# Voltage_Meter.net
KiCad netlist of a schematic drawn in Altium Designer
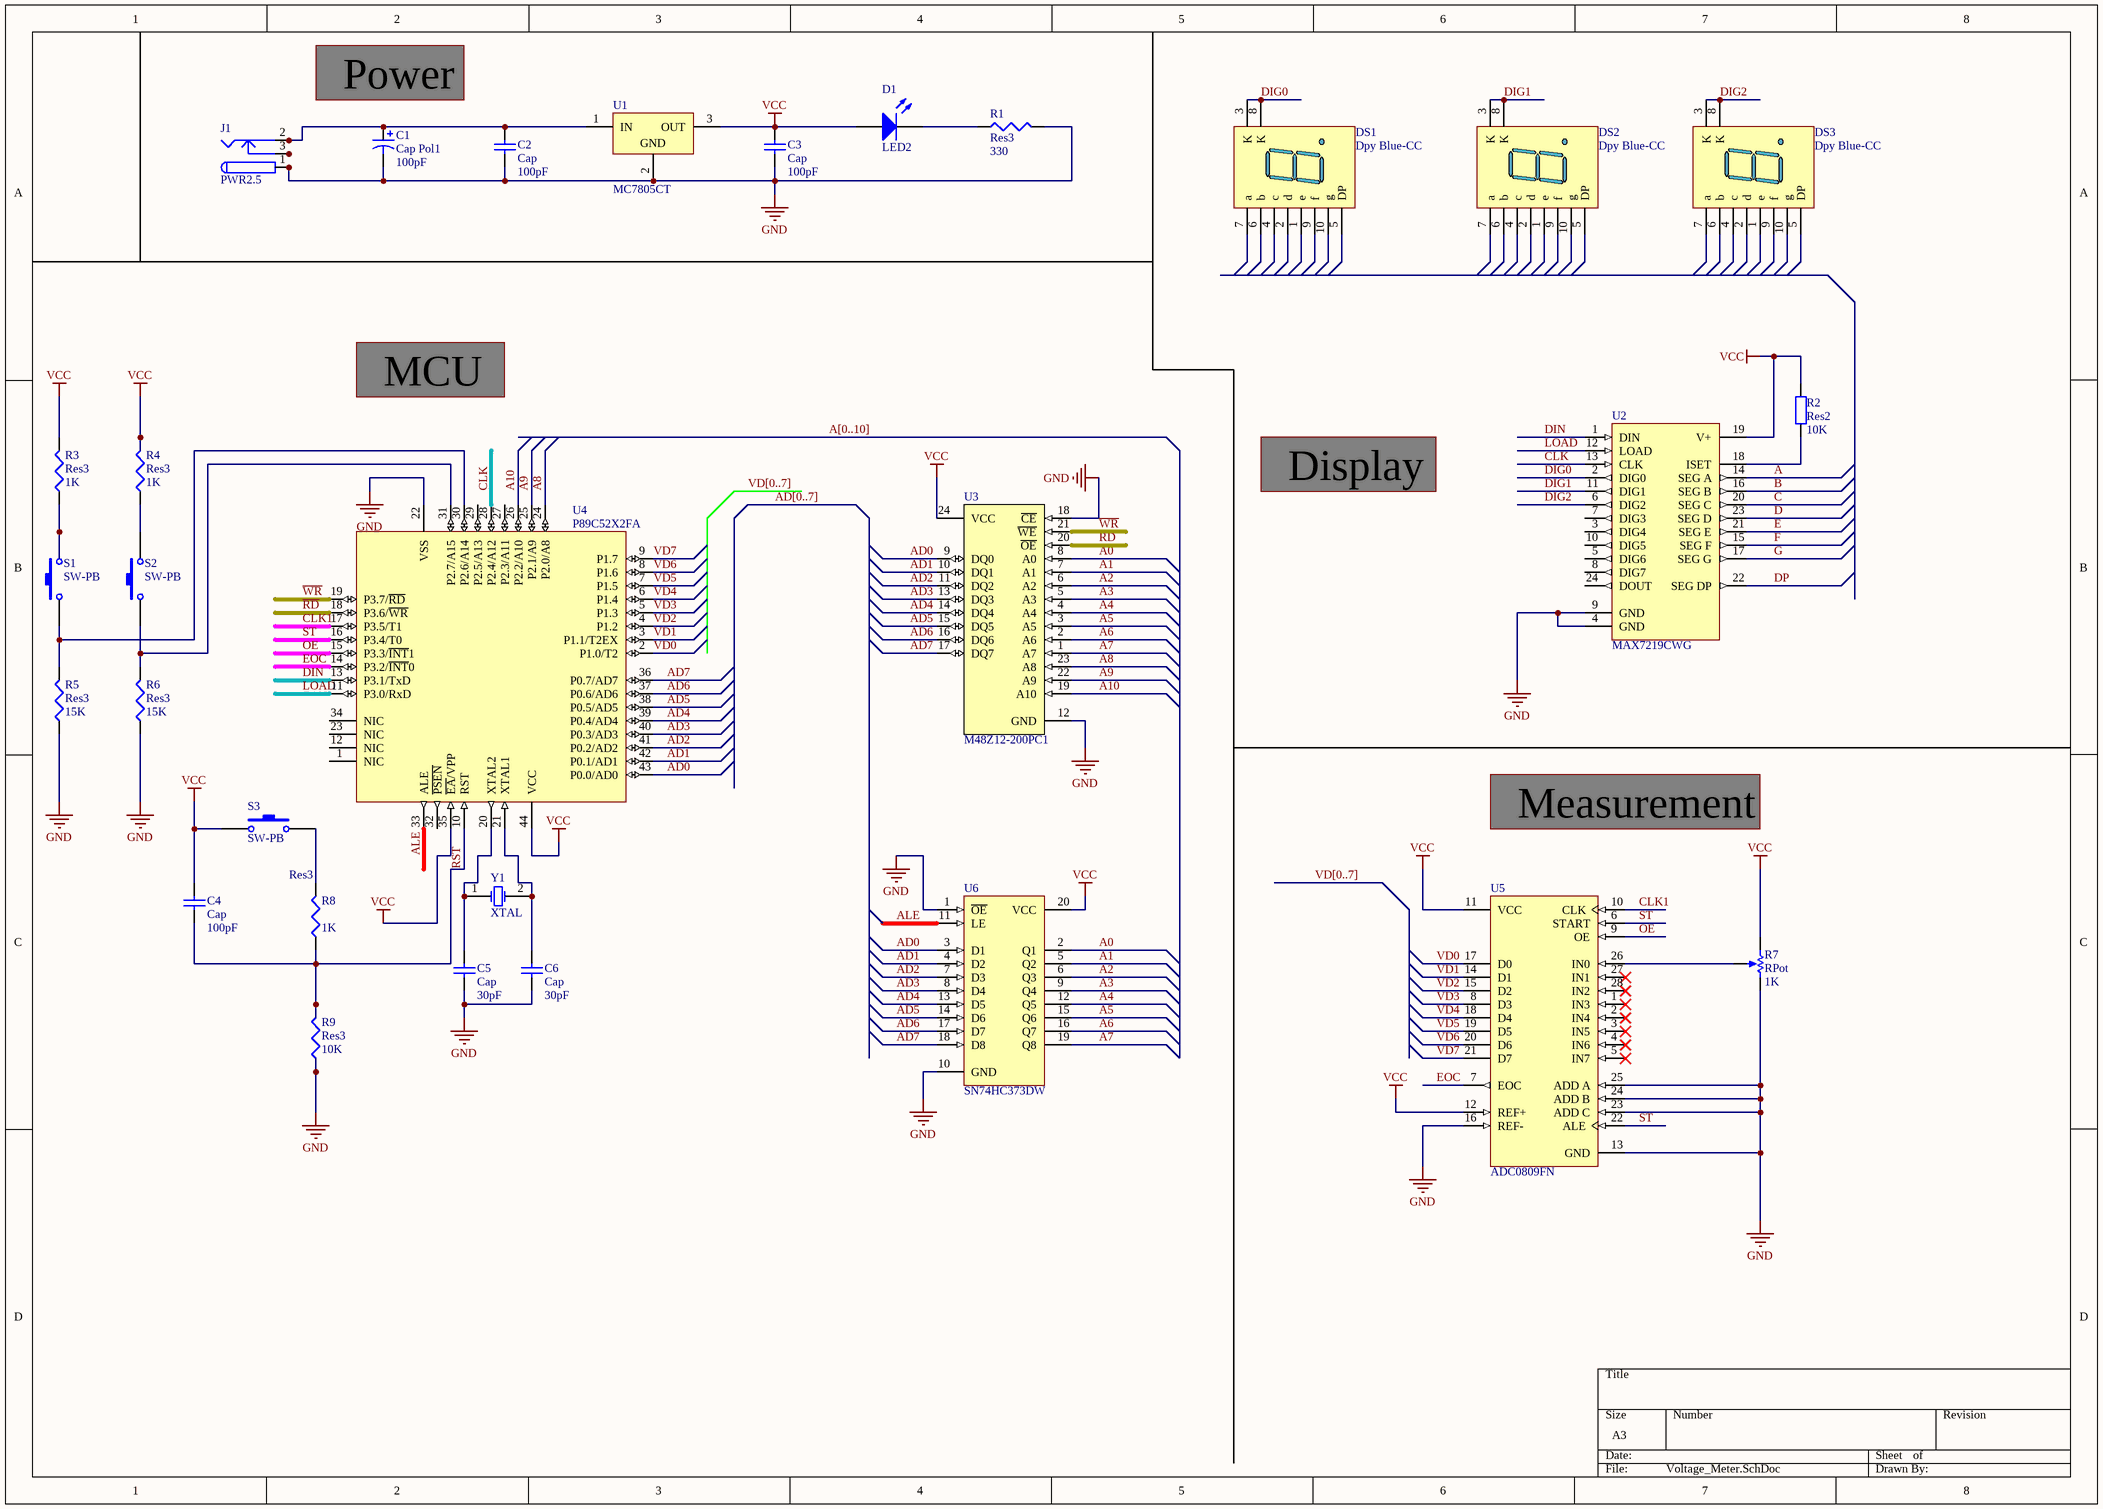
[diagram p0: Voltage_Meter.SchDoc]

(export (version "E")
  (design (tool "Eeschema 10.0.6"))
  (components
    (comp (ref "C1")
      (value "Cap Pol1")
      (footprint "RB7.6-15")
      (description "Polarized Capacitor (Radial)")
      (fields (field (name "ALTIUM_VALUE") "100pF") (field (name "PUBLISHER") "Altium Limited"))
      (libsource (lib "Miscellaneous Devices") (part "Cap Pol1"))
    )
    (comp (ref "C2")
      (value "Cap")
      (footprint "RAD-0.3")
      (description "Capacitor")
      (fields (field (name "ALTIUM_VALUE") "100pF") (field (name "PUBLISHER") "Altium Limited"))
      (libsource (lib "Miscellaneous Devices") (part "Cap"))
    )
    (comp (ref "C3")
      (value "Cap")
      (footprint "RAD-0.3")
      (description "Capacitor")
      (fields (field (name "ALTIUM_VALUE") "100pF") (field (name "PUBLISHER") "Altium Limited"))
      (libsource (lib "Miscellaneous Devices") (part "Cap"))
    )
    (comp (ref "C4")
      (value "Cap")
      (footprint "RAD-0.3")
      (description "Capacitor")
      (fields (field (name "ALTIUM_VALUE") "100pF") (field (name "PUBLISHER") "Altium Limited"))
      (libsource (lib "Miscellaneous Devices") (part "Cap"))
    )
    (comp (ref "C5")
      (value "Cap")
      (footprint "RAD-0.3")
      (description "Capacitor")
      (fields (field (name "ALTIUM_VALUE") "30pF") (field (name "PUBLISHER") "Altium Limited"))
      (libsource (lib "Miscellaneous Devices") (part "Cap"))
    )
    (comp (ref "C6")
      (value "Cap")
      (footprint "RAD-0.3")
      (description "Capacitor")
      (fields (field (name "ALTIUM_VALUE") "30pF") (field (name "PUBLISHER") "Altium Limited"))
      (libsource (lib "Miscellaneous Devices") (part "Cap"))
    )
    (comp (ref "D1")
      (value "LED2")
      (footprint "3.2X1.6X1.1")
      (description "Typical RED, GREEN, YELLOW, AMBER GaAs LED")
      (fields (field (name "PUBLISHER") "Altium Limited"))
      (libsource (lib "Miscellaneous Devices") (part "LED2"))
    )
    (comp (ref "DS1")
      (value "Dpy Blue-CC")
      (footprint "H")
      (description "14.2 mm General Purpose Blue 7-Segment Display: CC, RH DP, Gray Surface")
      (fields (field (name "PUBLISHER") "Altium Limited"))
      (libsource (lib "Miscellaneous Devices") (part "Dpy Blue-CC"))
    )
    (comp (ref "DS2")
      (value "Dpy Blue-CC")
      (footprint "H")
      (description "14.2 mm General Purpose Blue 7-Segment Display: CC, RH DP, Gray Surface")
      (fields (field (name "PUBLISHER") "Altium Limited"))
      (libsource (lib "Miscellaneous Devices") (part "Dpy Blue-CC"))
    )
    (comp (ref "DS3")
      (value "Dpy Blue-CC")
      (footprint "H")
      (description "14.2 mm General Purpose Blue 7-Segment Display: CC, RH DP, Gray Surface")
      (fields (field (name "PUBLISHER") "Altium Limited"))
      (libsource (lib "Miscellaneous Devices") (part "Dpy Blue-CC"))
    )
    (comp (ref "J1")
      (value "PWR2.5")
      (footprint "KLD-0202")
      (description "Low Voltage Power Supply Connector")
      (fields (field (name "PUBLISHER") "Altium Limited"))
      (libsource (lib "Miscellaneous Connectors") (part "PWR2.5"))
    )
    (comp (ref "R1")
      (value "Res3")
      (footprint "J1-0603")
      (description "Resistor")
      (fields (field (name "ALTIUM_VALUE") "330") (field (name "PUBLISHER") "Altium Limited"))
      (libsource (lib "Miscellaneous Devices") (part "Res3"))
    )
    (comp (ref "R2")
      (value "Res2")
      (footprint "AXIAL-0.4")
      (description "Resistor")
      (fields (field (name "ALTIUM_VALUE") "10K") (field (name "PUBLISHER") "Altium Limited"))
      (libsource (lib "Miscellaneous Devices") (part "Res2"))
    )
    (comp (ref "R3")
      (value "Res3")
      (footprint "J1-0603")
      (description "Resistor")
      (fields (field (name "ALTIUM_VALUE") "1K") (field (name "PUBLISHER") "Altium Limited"))
      (libsource (lib "Miscellaneous Devices") (part "Res3"))
    )
    (comp (ref "R4")
      (value "Res3")
      (footprint "J1-0603")
      (description "Resistor")
      (fields (field (name "ALTIUM_VALUE") "1K") (field (name "PUBLISHER") "Altium Limited"))
      (libsource (lib "Miscellaneous Devices") (part "Res3"))
    )
    (comp (ref "R5")
      (value "Res3")
      (footprint "J1-0603")
      (description "Resistor")
      (fields (field (name "ALTIUM_VALUE") "15K") (field (name "PUBLISHER") "Altium Limited"))
      (libsource (lib "Miscellaneous Devices") (part "Res3"))
    )
    (comp (ref "R6")
      (value "Res3")
      (footprint "J1-0603")
      (description "Resistor")
      (fields (field (name "ALTIUM_VALUE") "15K") (field (name "PUBLISHER") "Altium Limited"))
      (libsource (lib "Miscellaneous Devices") (part "Res3"))
    )
    (comp (ref "R7")
      (value "RPot")
      (footprint "VR5")
      (description "Potentiometer")
      (fields (field (name "ALTIUM_VALUE") "1K") (field (name "PUBLISHER") "Altium Limited"))
      (libsource (lib "Miscellaneous Devices") (part "RPot"))
    )
    (comp (ref "R8")
      (value "Res3")
      (footprint "J1-0603")
      (description "Resistor")
      (fields (field (name "ALTIUM_VALUE") "1K") (field (name "PUBLISHER") "Altium Limited"))
      (libsource (lib "Miscellaneous Devices") (part "Res3"))
    )
    (comp (ref "R9")
      (value "Res3")
      (footprint "J1-0603")
      (description "Resistor")
      (fields (field (name "ALTIUM_VALUE") "10K") (field (name "PUBLISHER") "Altium Limited"))
      (libsource (lib "Miscellaneous Devices") (part "Res3"))
    )
    (comp (ref "S1")
      (value "SW-PB")
      (footprint "SPST-2")
      (description "Switch")
      (fields (field (name "PUBLISHER") "Altium Limited"))
      (libsource (lib "Miscellaneous Devices") (part "SW-PB"))
    )
    (comp (ref "S2")
      (value "SW-PB")
      (footprint "SPST-2")
      (description "Switch")
      (fields (field (name "PUBLISHER") "Altium Limited"))
      (libsource (lib "Miscellaneous Devices") (part "SW-PB"))
    )
    (comp (ref "S3")
      (value "SW-PB")
      (footprint "SPST-2")
      (description "Switch")
      (fields (field (name "PUBLISHER") "Altium Limited"))
      (libsource (lib "Miscellaneous Devices") (part "SW-PB"))
    )
    (comp (ref "U1")
      (value "MC7805CT")
      (footprint "221A-04")
      (description "3-Terminal Positive Fixed Voltage Regulator")
      (fields (field (name "PUBLISHER") "Altium Limited"))
      (libsource (lib "Motorola Power Mgt Voltage Regulator") (part "MC7805CT"))
    )
    (comp (ref "U2")
      (value "MAX7219CWG")
      (footprint "WSO24_N")
      (description "Serially Interfaced, 8-Digit LED Display Driver")
      (fields (field (name "PUBLISHER") "Altium Limited"))
      (libsource (lib "Maxim Interface Display Driver") (part "MAX7219CWG"))
    )
    (comp (ref "U3")
      (value "M48Z12-200PC1")
      (footprint "PCDIP24")
      (description "16 Kbit (2Kb x 8) Zeropower SRAM")
      (fields (field (name "PUBLISHER") "Altium Limited"))
      (libsource (lib "ST Memory Non-Volatile RAM") (part "M48Z12-200PC1"))
    )
    (comp (ref "U4")
      (value "P89C52X2FA")
      (footprint "SOT187-2_N")
      (description "80C51 8-Bit Flash Microcontroller Family, 8 kB Flash")
      (fields (field (name "PUBLISHER") "Altium Limited"))
      (libsource (lib "Philips Microcontroller 8-Bit") (part "P89C52X2FA"))
    )
    (comp (ref "U5")
      (value "ADC0809FN")
      (footprint "FN028_N")
      (description "CMOS Analog-to-Digital Converter with 8-Channel Multiplexer")
      (fields (field (name "PUBLISHER") "Altium Limited"))
      (libsource (lib "TI Converter Analog to Digital") (part "ADC0809FN"))
    )
    (comp (ref "U6")
      (value "SN74HC373DW")
      (footprint "DW020_N")
      (description "Octal Transparent D-Type Latches with 3-State Outputs")
      (fields (field (name "PUBLISHER") "Altium Limited"))
      (libsource (lib "TI Logic Latch") (part "SN74HC373DW"))
    )
    (comp (ref "Y1")
      (value "XTAL")
      (footprint "R38")
      (description "Crystal Oscillator")
      (fields (field (name "PUBLISHER") "Altium Limited"))
      (libsource (lib "Miscellaneous Devices") (part "XTAL"))
    )
  )
  (nets
    (net (code "1") (name "/A") (class "Default")
      (node (ref "U2") (pin "14") (pinfunction "SEG_A_14") (pintype "output"))
    )
    (net (code "2") (name "/A0") (class "Default")
      (node (ref "U3") (pin "8") (pinfunction "A0_8") (pintype "input"))
      (node (ref "U6") (pin "2") (pinfunction "Q1_2") (pintype "tri_state"))
    )
    (net (code "3") (name "/A1") (class "Default")
      (node (ref "U3") (pin "7") (pinfunction "A1_7") (pintype "input"))
      (node (ref "U6") (pin "5") (pinfunction "Q2_5") (pintype "tri_state"))
    )
    (net (code "4") (name "/A2") (class "Default")
      (node (ref "U3") (pin "6") (pinfunction "A2_6") (pintype "input"))
      (node (ref "U6") (pin "6") (pinfunction "Q3_6") (pintype "tri_state"))
    )
    (net (code "5") (name "/A3") (class "Default")
      (node (ref "U3") (pin "5") (pinfunction "A3_5") (pintype "input"))
      (node (ref "U6") (pin "9") (pinfunction "Q4_9") (pintype "tri_state"))
    )
    (net (code "6") (name "/A4") (class "Default")
      (node (ref "U3") (pin "4") (pinfunction "A4_4") (pintype "input"))
      (node (ref "U6") (pin "12") (pinfunction "Q5_12") (pintype "tri_state"))
    )
    (net (code "7") (name "/A5") (class "Default")
      (node (ref "U3") (pin "3") (pinfunction "A5_3") (pintype "input"))
      (node (ref "U6") (pin "15") (pinfunction "Q6_15") (pintype "tri_state"))
    )
    (net (code "8") (name "/A6") (class "Default")
      (node (ref "U3") (pin "2") (pinfunction "A6_2") (pintype "input"))
      (node (ref "U6") (pin "16") (pinfunction "Q7_16") (pintype "tri_state"))
    )
    (net (code "9") (name "/A7") (class "Default")
      (node (ref "U3") (pin "1") (pinfunction "A7_1") (pintype "input"))
      (node (ref "U6") (pin "19") (pinfunction "Q8_19") (pintype "tri_state"))
    )
    (net (code "10") (name "/A8") (class "Default")
      (node (ref "U3") (pin "23") (pinfunction "A8_23") (pintype "input"))
      (node (ref "U4") (pin "24") (pinfunction "P2.0/A8_24") (pintype "bidirectional"))
    )
    (net (code "11") (name "/A9") (class "Default")
      (node (ref "U3") (pin "22") (pinfunction "A9_22") (pintype "input"))
      (node (ref "U4") (pin "25") (pinfunction "P2.1/A9_25") (pintype "bidirectional"))
    )
    (net (code "12") (name "/A10") (class "Default")
      (node (ref "U3") (pin "19") (pinfunction "A10_19") (pintype "input"))
      (node (ref "U4") (pin "26") (pinfunction "P2.2/A10_26") (pintype "bidirectional"))
    )
    (net (code "13") (name "/AD0") (class "Default")
      (node (ref "U3") (pin "9") (pinfunction "DQ0_9") (pintype "bidirectional"))
      (node (ref "U4") (pin "43") (pinfunction "P0.0/AD0_43") (pintype "bidirectional"))
      (node (ref "U6") (pin "3") (pinfunction "D1_3") (pintype "input"))
    )
    (net (code "14") (name "/AD1") (class "Default")
      (node (ref "U3") (pin "10") (pinfunction "DQ1_10") (pintype "bidirectional"))
      (node (ref "U4") (pin "42") (pinfunction "P0.1/AD1_42") (pintype "bidirectional"))
      (node (ref "U6") (pin "4") (pinfunction "D2_4") (pintype "input"))
    )
    (net (code "15") (name "/AD2") (class "Default")
      (node (ref "U3") (pin "11") (pinfunction "DQ2_11") (pintype "bidirectional"))
      (node (ref "U4") (pin "41") (pinfunction "P0.2/AD2_41") (pintype "bidirectional"))
      (node (ref "U6") (pin "7") (pinfunction "D3_7") (pintype "input"))
    )
    (net (code "16") (name "/AD3") (class "Default")
      (node (ref "U3") (pin "13") (pinfunction "DQ3_13") (pintype "bidirectional"))
      (node (ref "U4") (pin "40") (pinfunction "P0.3/AD3_40") (pintype "bidirectional"))
      (node (ref "U6") (pin "8") (pinfunction "D4_8") (pintype "input"))
    )
    (net (code "17") (name "/AD4") (class "Default")
      (node (ref "U3") (pin "14") (pinfunction "DQ4_14") (pintype "bidirectional"))
      (node (ref "U4") (pin "39") (pinfunction "P0.4/AD4_39") (pintype "bidirectional"))
      (node (ref "U6") (pin "13") (pinfunction "D5_13") (pintype "input"))
    )
    (net (code "18") (name "/AD5") (class "Default")
      (node (ref "U3") (pin "15") (pinfunction "DQ5_15") (pintype "bidirectional"))
      (node (ref "U4") (pin "38") (pinfunction "P0.5/AD5_38") (pintype "bidirectional"))
      (node (ref "U6") (pin "14") (pinfunction "D6_14") (pintype "input"))
    )
    (net (code "19") (name "/AD6") (class "Default")
      (node (ref "U3") (pin "16") (pinfunction "DQ6_16") (pintype "bidirectional"))
      (node (ref "U4") (pin "37") (pinfunction "P0.6/AD6_37") (pintype "bidirectional"))
      (node (ref "U6") (pin "17") (pinfunction "D7_17") (pintype "input"))
    )
    (net (code "20") (name "/AD7") (class "Default")
      (node (ref "U3") (pin "17") (pinfunction "DQ7_17") (pintype "bidirectional"))
      (node (ref "U4") (pin "36") (pinfunction "P0.7/AD7_36") (pintype "bidirectional"))
      (node (ref "U6") (pin "18") (pinfunction "D8_18") (pintype "input"))
    )
    (net (code "22") (name "/ALE") (class "Default")
      (node (ref "U4") (pin "33") (pinfunction "ALE_33") (pintype "output"))
      (node (ref "U6") (pin "11") (pinfunction "LE_11") (pintype "input"))
    )
    (net (code "24") (name "/B") (class "Default")
      (node (ref "U2") (pin "16") (pinfunction "SEG_B_16") (pintype "output"))
    )
    (net (code "25") (name "/C") (class "Default")
      (node (ref "U2") (pin "20") (pinfunction "SEG_C_20") (pintype "output"))
    )
    (net (code "26") (name "/CLK") (class "Default")
      (node (ref "U2") (pin "13") (pinfunction "CLK_13") (pintype "input"))
      (node (ref "U4") (pin "28") (pinfunction "P2.4/A12_28") (pintype "bidirectional"))
    )
    (net (code "27") (name "/CLK1") (class "Default")
      (node (ref "U4") (pin "17") (pinfunction "P3.5/T1_17") (pintype "bidirectional"))
      (node (ref "U5") (pin "10") (pinfunction "CLK_10") (pintype "input"))
    )
    (net (code "28") (name "/D") (class "Default")
      (node (ref "U2") (pin "23") (pinfunction "SEG_D_23") (pintype "output"))
    )
    (net (code "29") (name "/DIG0") (class "Default")
      (node (ref "DS1") (pin "3") (pinfunction "K_3") (pintype "passive"))
      (node (ref "DS1") (pin "8") (pinfunction "K_8") (pintype "passive"))
      (node (ref "U2") (pin "2") (pinfunction "DIG0_2") (pintype "output"))
    )
    (net (code "30") (name "/DIG1") (class "Default")
      (node (ref "DS2") (pin "3") (pinfunction "K_3") (pintype "passive"))
      (node (ref "DS2") (pin "8") (pinfunction "K_8") (pintype "passive"))
      (node (ref "U2") (pin "11") (pinfunction "DIG1_11") (pintype "output"))
    )
    (net (code "31") (name "/DIG2") (class "Default")
      (node (ref "DS3") (pin "3") (pinfunction "K_3") (pintype "passive"))
      (node (ref "DS3") (pin "8") (pinfunction "K_8") (pintype "passive"))
      (node (ref "U2") (pin "6") (pinfunction "DIG2_6") (pintype "output"))
    )
    (net (code "32") (name "/DIN") (class "Default")
      (node (ref "U2") (pin "1") (pinfunction "DIN_1") (pintype "input"))
      (node (ref "U4") (pin "13") (pinfunction "P3.1/TxD_13") (pintype "bidirectional"))
    )
    (net (code "33") (name "/DP") (class "Default")
      (node (ref "U2") (pin "22") (pinfunction "SEG_DP_22") (pintype "output"))
    )
    (net (code "35") (name "/E") (class "Default")
      (node (ref "U2") (pin "21") (pinfunction "SEG_E_21") (pintype "output"))
    )
    (net (code "36") (name "/EOC") (class "Default")
      (node (ref "U4") (pin "14") (pinfunction "P3.2/~{INT}0_14") (pintype "bidirectional"))
      (node (ref "U5") (pin "7") (pinfunction "EOC_7") (pintype "output"))
    )
    (net (code "37") (name "/F") (class "Default")
      (node (ref "U2") (pin "15") (pinfunction "SEG_F_15") (pintype "output"))
    )
    (net (code "38") (name "/G") (class "Default")
      (node (ref "U2") (pin "17") (pinfunction "SEG_G_17") (pintype "output"))
    )
    (net (code "39") (name "/LOAD") (class "Default")
      (node (ref "U2") (pin "12") (pinfunction "LOAD_12") (pintype "input"))
      (node (ref "U4") (pin "11") (pinfunction "P3.0/RxD_11") (pintype "bidirectional"))
    )
    (net (code "42") (name "/OE") (class "Default")
      (node (ref "U4") (pin "15") (pinfunction "P3.3/~{INT}1_15") (pintype "bidirectional"))
      (node (ref "U5") (pin "9") (pinfunction "OE_9") (pintype "input"))
    )
    (net (code "44") (name "/RST") (class "Default")
      (node (ref "C4") (pin "1") (pinfunction "1_1") (pintype "passive"))
      (node (ref "R8") (pin "1") (pinfunction "1_1") (pintype "passive"))
      (node (ref "R9") (pin "2") (pinfunction "2_2") (pintype "passive"))
      (node (ref "U4") (pin "10") (pinfunction "RST_10") (pintype "input"))
    )
    (net (code "45") (name "/ST") (class "Default")
      (node (ref "U4") (pin "16") (pinfunction "P3.4/T0_16") (pintype "bidirectional"))
      (node (ref "U5") (pin "22") (pinfunction "ALE_22") (pintype "input"))
      (node (ref "U5") (pin "6") (pinfunction "START_6") (pintype "input"))
    )
    (net (code "46") (name "/VD0") (class "Default")
      (node (ref "U4") (pin "2") (pinfunction "P1.0/T2_2") (pintype "bidirectional"))
      (node (ref "U5") (pin "17") (pinfunction "D0_17") (pintype "tri_state"))
    )
    (net (code "47") (name "/VD1") (class "Default")
      (node (ref "U4") (pin "3") (pinfunction "P1.1/T2EX_3") (pintype "bidirectional"))
      (node (ref "U5") (pin "14") (pinfunction "D1_14") (pintype "tri_state"))
    )
    (net (code "48") (name "/VD2") (class "Default")
      (node (ref "U4") (pin "4") (pinfunction "P1.2_4") (pintype "bidirectional"))
      (node (ref "U5") (pin "15") (pinfunction "D2_15") (pintype "tri_state"))
    )
    (net (code "49") (name "/VD3") (class "Default")
      (node (ref "U4") (pin "5") (pinfunction "P1.3_5") (pintype "bidirectional"))
      (node (ref "U5") (pin "8") (pinfunction "D3_8") (pintype "tri_state"))
    )
    (net (code "50") (name "/VD4") (class "Default")
      (node (ref "U4") (pin "6") (pinfunction "P1.4_6") (pintype "bidirectional"))
      (node (ref "U5") (pin "18") (pinfunction "D4_18") (pintype "tri_state"))
    )
    (net (code "51") (name "/VD5") (class "Default")
      (node (ref "U4") (pin "7") (pinfunction "P1.5_7") (pintype "bidirectional"))
      (node (ref "U5") (pin "19") (pinfunction "D5_19") (pintype "tri_state"))
    )
    (net (code "52") (name "/VD6") (class "Default")
      (node (ref "U4") (pin "8") (pinfunction "P1.6_8") (pintype "bidirectional"))
      (node (ref "U5") (pin "20") (pinfunction "D6_20") (pintype "tri_state"))
    )
    (net (code "53") (name "/VD7") (class "Default")
      (node (ref "U4") (pin "9") (pinfunction "P1.7_9") (pintype "bidirectional"))
      (node (ref "U5") (pin "21") (pinfunction "D7_21") (pintype "tri_state"))
    )
    (net (code "55") (name "/~{RD}") (class "Default")
      (node (ref "U3") (pin "20") (pinfunction "~{OE}_20") (pintype "input"))
      (node (ref "U4") (pin "18") (pinfunction "P3.6/~{WR}_18") (pintype "bidirectional"))
    )
    (net (code "56") (name "/~{WR}") (class "Default")
      (node (ref "U3") (pin "21") (pinfunction "~{WE}_21") (pintype "input"))
      (node (ref "U4") (pin "19") (pinfunction "P3.7/~{RD}_19") (pintype "bidirectional"))
    )
    (net (code "57") (name "GND") (class "Default")
      (node (ref "C1") (pin "2") (pinfunction "2_2") (pintype "passive"))
      (node (ref "C2") (pin "1") (pinfunction "1_1") (pintype "passive"))
      (node (ref "C3") (pin "1") (pinfunction "1_1") (pintype "passive"))
      (node (ref "C5") (pin "1") (pinfunction "1_1") (pintype "passive"))
      (node (ref "C6") (pin "1") (pinfunction "1_1") (pintype "passive"))
      (node (ref "J1") (pin "1") (pinfunction "1_1") (pintype "power_in"))
      (node (ref "J1") (pin "1A") (pinfunction "1A_1A") (pintype "power_in"))
      (node (ref "J1") (pin "1B") (pinfunction "1B_1B") (pintype "power_in"))
      (node (ref "R1") (pin "2") (pinfunction "2_2") (pintype "passive"))
      (node (ref "R5") (pin "1") (pinfunction "1_1") (pintype "passive"))
      (node (ref "R6") (pin "1") (pinfunction "1_1") (pintype "passive"))
      (node (ref "R7") (pin "2") (pinfunction "BOT_2") (pintype "passive"))
      (node (ref "R9") (pin "1") (pinfunction "1_1") (pintype "passive"))
      (node (ref "U1") (pin "2") (pinfunction "GND_2") (pintype "power_in"))
      (node (ref "U2") (pin "4") (pinfunction "GND_4") (pintype "power_in"))
      (node (ref "U2") (pin "9") (pinfunction "GND_9") (pintype "power_in"))
      (node (ref "U3") (pin "12") (pinfunction "GND_12") (pintype "power_in"))
      (node (ref "U3") (pin "18") (pinfunction "~{CE}_18") (pintype "input"))
      (node (ref "U4") (pin "22") (pinfunction "VSS_22") (pintype "power_in"))
      (node (ref "U5") (pin "13") (pinfunction "GND_13") (pintype "power_in"))
      (node (ref "U5") (pin "16") (pinfunction "REF-_16") (pintype "input"))
      (node (ref "U5") (pin "23") (pinfunction "ADD_C_23") (pintype "input"))
      (node (ref "U5") (pin "24") (pinfunction "ADD_B_24") (pintype "input"))
      (node (ref "U5") (pin "25") (pinfunction "ADD_A_25") (pintype "input"))
      (node (ref "U6") (pin "1") (pinfunction "~{OE}_1") (pintype "input"))
      (node (ref "U6") (pin "10") (pinfunction "GND_10") (pintype "power_in"))
    )
    (net (code "58") (name "Net-(D1-K)") (class "Default")
      (node (ref "D1") (pin "2") (pinfunction "K_2") (pintype "passive"))
      (node (ref "R1") (pin "1") (pinfunction "1_1") (pintype "passive"))
    )
    (net (code "59") (name "Net-(J1-Pad3)") (class "Default")
      (node (ref "J1") (pin "3") (pinfunction "3_3") (pintype "power_in"))
      (node (ref "J1") (pin "3A") (pinfunction "3A_3A") (pintype "power_in"))
      (node (ref "J1") (pin "3B") (pinfunction "3B_3B") (pintype "power_in"))
    )
    (net (code "60") (name "Net-(R3-Pad1)") (class "Default")
      (node (ref "R3") (pin "1") (pinfunction "1_1") (pintype "passive"))
      (node (ref "S1") (pin "2") (pinfunction "2_2") (pintype "passive"))
    )
    (net (code "61") (name "Net-(R4-Pad1)") (class "Default")
      (node (ref "R4") (pin "1") (pinfunction "1_1") (pintype "passive"))
      (node (ref "S2") (pin "2") (pinfunction "2_2") (pintype "passive"))
    )
    (net (code "62") (name "Net-(R7-TAP)") (class "Default")
      (node (ref "R7") (pin "3") (pinfunction "TAP_3") (pintype "passive"))
      (node (ref "U5") (pin "26") (pinfunction "IN0_26") (pintype "input"))
    )
    (net (code "63") (name "Net-(R8-Pad2)") (class "Default")
      (node (ref "R8") (pin "2") (pinfunction "2_2") (pintype "passive"))
      (node (ref "S3") (pin "2") (pinfunction "2_2") (pintype "passive"))
    )
    (net (code "64") (name "Net-(U1-IN)") (class "Default")
      (node (ref "C1") (pin "1") (pinfunction "1_1") (pintype "passive"))
      (node (ref "C2") (pin "2") (pinfunction "2_2") (pintype "passive"))
      (node (ref "J1") (pin "2") (pinfunction "2_2") (pintype "power_in"))
      (node (ref "J1") (pin "2A") (pinfunction "2A_2A") (pintype "power_in"))
      (node (ref "J1") (pin "2B") (pinfunction "2B_2B") (pintype "power_in"))
      (node (ref "U1") (pin "1") (pinfunction "IN_1") (pintype "power_in"))
    )
    (net (code "65") (name "Net-(U2-ISET)") (class "Default")
      (node (ref "R2") (pin "1") (pinfunction "1_1") (pintype "passive"))
      (node (ref "U2") (pin "18") (pinfunction "ISET_18") (pintype "passive"))
    )
    (net (code "66") (name "Net-(U4-P2.6{slash}A14)") (class "Default")
      (node (ref "R5") (pin "2") (pinfunction "2_2") (pintype "passive"))
      (node (ref "S1") (pin "1") (pinfunction "1_1") (pintype "passive"))
      (node (ref "U4") (pin "30") (pinfunction "P2.6/A14_30") (pintype "bidirectional"))
    )
    (net (code "67") (name "Net-(U4-P2.7{slash}A15)") (class "Default")
      (node (ref "R6") (pin "2") (pinfunction "2_2") (pintype "passive"))
      (node (ref "S2") (pin "1") (pinfunction "1_1") (pintype "passive"))
      (node (ref "U4") (pin "31") (pinfunction "P2.7/A15_31") (pintype "bidirectional"))
    )
    (net (code "68") (name "Net-(U4-XTAL1)") (class "Default")
      (node (ref "C6") (pin "2") (pinfunction "2_2") (pintype "passive"))
      (node (ref "U4") (pin "21") (pinfunction "XTAL1_21") (pintype "input"))
      (node (ref "Y1") (pin "2") (pinfunction "OSC2_2") (pintype "passive"))
    )
    (net (code "69") (name "Net-(U4-XTAL2)") (class "Default")
      (node (ref "C5") (pin "2") (pinfunction "2_2") (pintype "passive"))
      (node (ref "U4") (pin "20") (pinfunction "XTAL2_20") (pintype "output"))
      (node (ref "Y1") (pin "1") (pinfunction "OSC1_1") (pintype "passive"))
    )
    (net (code "70") (name "VCC") (class "Default")
      (node (ref "C3") (pin "2") (pinfunction "2_2") (pintype "passive"))
      (node (ref "C4") (pin "2") (pinfunction "2_2") (pintype "passive"))
      (node (ref "D1") (pin "1") (pinfunction "A_1") (pintype "passive"))
      (node (ref "R2") (pin "2") (pinfunction "2_2") (pintype "passive"))
      (node (ref "R3") (pin "2") (pinfunction "2_2") (pintype "passive"))
      (node (ref "R4") (pin "2") (pinfunction "2_2") (pintype "passive"))
      (node (ref "R7") (pin "1") (pinfunction "TOP_1") (pintype "passive"))
      (node (ref "S3") (pin "1") (pinfunction "1_1") (pintype "passive"))
      (node (ref "U1") (pin "3") (pinfunction "OUT_3") (pintype "power_in"))
      (node (ref "U2") (pin "19") (pinfunction "V+_19") (pintype "power_in"))
      (node (ref "U3") (pin "24") (pinfunction "VCC_24") (pintype "power_in"))
      (node (ref "U4") (pin "35") (pinfunction "~{EA}/VPP_35") (pintype "input"))
      (node (ref "U4") (pin "44") (pinfunction "VCC_44") (pintype "power_in"))
      (node (ref "U5") (pin "11") (pinfunction "VCC_11") (pintype "power_in"))
      (node (ref "U5") (pin "12") (pinfunction "REF+_12") (pintype "input"))
      (node (ref "U6") (pin "20") (pinfunction "VCC_20") (pintype "power_in"))
    )
    (net (code "71") (name "unconnected-(DS1-DP-Pad5)") (class "Default")
      (node (ref "DS1") (pin "5") (pinfunction "DP_5") (pintype "passive"))
    )
    (net (code "72") (name "unconnected-(DS1-a-Pad7)") (class "Default")
      (node (ref "DS1") (pin "7") (pinfunction "a_7") (pintype "passive"))
    )
    (net (code "73") (name "unconnected-(DS1-b-Pad6)") (class "Default")
      (node (ref "DS1") (pin "6") (pinfunction "b_6") (pintype "passive"))
    )
    (net (code "74") (name "unconnected-(DS1-c-Pad4)") (class "Default")
      (node (ref "DS1") (pin "4") (pinfunction "c_4") (pintype "passive"))
    )
    (net (code "75") (name "unconnected-(DS1-d-Pad2)") (class "Default")
      (node (ref "DS1") (pin "2") (pinfunction "d_2") (pintype "passive"))
    )
    (net (code "76") (name "unconnected-(DS1-e-Pad1)") (class "Default")
      (node (ref "DS1") (pin "1") (pinfunction "e_1") (pintype "passive"))
    )
    (net (code "77") (name "unconnected-(DS1-f-Pad9)") (class "Default")
      (node (ref "DS1") (pin "9") (pinfunction "f_9") (pintype "passive"))
    )
    (net (code "78") (name "unconnected-(DS1-g-Pad10)") (class "Default")
      (node (ref "DS1") (pin "10") (pinfunction "g_10") (pintype "passive"))
    )
    (net (code "79") (name "unconnected-(DS2-DP-Pad5)") (class "Default")
      (node (ref "DS2") (pin "5") (pinfunction "DP_5") (pintype "passive"))
    )
    (net (code "80") (name "unconnected-(DS2-a-Pad7)") (class "Default")
      (node (ref "DS2") (pin "7") (pinfunction "a_7") (pintype "passive"))
    )
    (net (code "81") (name "unconnected-(DS2-b-Pad6)") (class "Default")
      (node (ref "DS2") (pin "6") (pinfunction "b_6") (pintype "passive"))
    )
    (net (code "82") (name "unconnected-(DS2-c-Pad4)") (class "Default")
      (node (ref "DS2") (pin "4") (pinfunction "c_4") (pintype "passive"))
    )
    (net (code "83") (name "unconnected-(DS2-d-Pad2)") (class "Default")
      (node (ref "DS2") (pin "2") (pinfunction "d_2") (pintype "passive"))
    )
    (net (code "84") (name "unconnected-(DS2-e-Pad1)") (class "Default")
      (node (ref "DS2") (pin "1") (pinfunction "e_1") (pintype "passive"))
    )
    (net (code "85") (name "unconnected-(DS2-f-Pad9)") (class "Default")
      (node (ref "DS2") (pin "9") (pinfunction "f_9") (pintype "passive"))
    )
    (net (code "86") (name "unconnected-(DS2-g-Pad10)") (class "Default")
      (node (ref "DS2") (pin "10") (pinfunction "g_10") (pintype "passive"))
    )
    (net (code "87") (name "unconnected-(DS3-DP-Pad5)") (class "Default")
      (node (ref "DS3") (pin "5") (pinfunction "DP_5") (pintype "passive"))
    )
    (net (code "88") (name "unconnected-(DS3-a-Pad7)") (class "Default")
      (node (ref "DS3") (pin "7") (pinfunction "a_7") (pintype "passive"))
    )
    (net (code "89") (name "unconnected-(DS3-b-Pad6)") (class "Default")
      (node (ref "DS3") (pin "6") (pinfunction "b_6") (pintype "passive"))
    )
    (net (code "90") (name "unconnected-(DS3-c-Pad4)") (class "Default")
      (node (ref "DS3") (pin "4") (pinfunction "c_4") (pintype "passive"))
    )
    (net (code "91") (name "unconnected-(DS3-d-Pad2)") (class "Default")
      (node (ref "DS3") (pin "2") (pinfunction "d_2") (pintype "passive"))
    )
    (net (code "92") (name "unconnected-(DS3-e-Pad1)") (class "Default")
      (node (ref "DS3") (pin "1") (pinfunction "e_1") (pintype "passive"))
    )
    (net (code "93") (name "unconnected-(DS3-f-Pad9)") (class "Default")
      (node (ref "DS3") (pin "9") (pinfunction "f_9") (pintype "passive"))
    )
    (net (code "94") (name "unconnected-(DS3-g-Pad10)") (class "Default")
      (node (ref "DS3") (pin "10") (pinfunction "g_10") (pintype "passive"))
    )
    (net (code "95") (name "unconnected-(U2-DIG3-Pad7)") (class "Default")
      (node (ref "U2") (pin "7") (pinfunction "DIG3_7") (pintype "output"))
    )
    (net (code "96") (name "unconnected-(U2-DIG4-Pad3)") (class "Default")
      (node (ref "U2") (pin "3") (pinfunction "DIG4_3") (pintype "output"))
    )
    (net (code "97") (name "unconnected-(U2-DIG5-Pad10)") (class "Default")
      (node (ref "U2") (pin "10") (pinfunction "DIG5_10") (pintype "output"))
    )
    (net (code "98") (name "unconnected-(U2-DIG6-Pad5)") (class "Default")
      (node (ref "U2") (pin "5") (pinfunction "DIG6_5") (pintype "output"))
    )
    (net (code "99") (name "unconnected-(U2-DIG7-Pad8)") (class "Default")
      (node (ref "U2") (pin "8") (pinfunction "DIG7_8") (pintype "output"))
    )
    (net (code "100") (name "unconnected-(U2-DOUT-Pad24)") (class "Default")
      (node (ref "U2") (pin "24") (pinfunction "DOUT_24") (pintype "output"))
    )
    (net (code "101") (name "unconnected-(U4-NIC-Pad1)") (class "Default")
      (node (ref "U4") (pin "1") (pinfunction "NIC_1") (pintype "passive"))
    )
    (net (code "102") (name "unconnected-(U4-NIC-Pad12)") (class "Default")
      (node (ref "U4") (pin "12") (pinfunction "NIC_12") (pintype "passive"))
    )
    (net (code "103") (name "unconnected-(U4-NIC-Pad23)") (class "Default")
      (node (ref "U4") (pin "23") (pinfunction "NIC_23") (pintype "passive"))
    )
    (net (code "104") (name "unconnected-(U4-NIC-Pad34)") (class "Default")
      (node (ref "U4") (pin "34") (pinfunction "NIC_34") (pintype "passive"))
    )
    (net (code "105") (name "unconnected-(U4-P2.3{slash}A11-Pad27)") (class "Default")
      (node (ref "U4") (pin "27") (pinfunction "P2.3/A11_27") (pintype "bidirectional"))
    )
    (net (code "106") (name "unconnected-(U4-P2.5{slash}A13-Pad29)") (class "Default")
      (node (ref "U4") (pin "29") (pinfunction "P2.5/A13_29") (pintype "bidirectional"))
    )
    (net (code "107") (name "unconnected-(U4-~{PSEN}-Pad32)") (class "Default")
      (node (ref "U4") (pin "32") (pinfunction "~{PSEN}_32") (pintype "output"))
    )
    (net (code "108") (name "unconnected-(U5-IN1-Pad27)") (class "Default")
      (node (ref "U5") (pin "27") (pinfunction "IN1_27") (pintype "input+no_connect"))
    )
    (net (code "109") (name "unconnected-(U5-IN2-Pad28)") (class "Default")
      (node (ref "U5") (pin "28") (pinfunction "IN2_28") (pintype "input+no_connect"))
    )
    (net (code "110") (name "unconnected-(U5-IN3-Pad1)") (class "Default")
      (node (ref "U5") (pin "1") (pinfunction "IN3_1") (pintype "input+no_connect"))
    )
    (net (code "111") (name "unconnected-(U5-IN4-Pad2)") (class "Default")
      (node (ref "U5") (pin "2") (pinfunction "IN4_2") (pintype "input+no_connect"))
    )
    (net (code "112") (name "unconnected-(U5-IN5-Pad3)") (class "Default")
      (node (ref "U5") (pin "3") (pinfunction "IN5_3") (pintype "input+no_connect"))
    )
    (net (code "113") (name "unconnected-(U5-IN6-Pad4)") (class "Default")
      (node (ref "U5") (pin "4") (pinfunction "IN6_4") (pintype "input+no_connect"))
    )
    (net (code "114") (name "unconnected-(U5-IN7-Pad5)") (class "Default")
      (node (ref "U5") (pin "5") (pinfunction "IN7_5") (pintype "input+no_connect"))
    )
  )
)
